# Connectors.net
KiCad netlist of a schematic drawn in Altium Designer
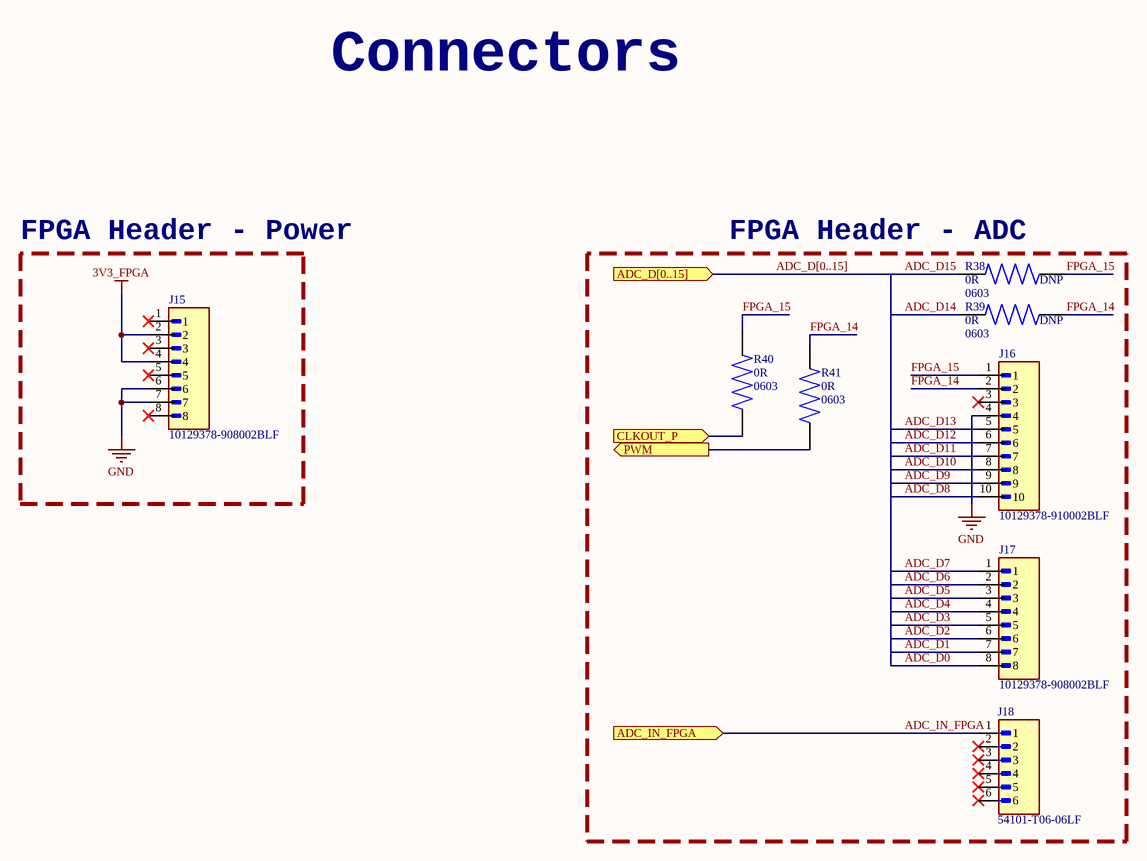
[diagram p0: Connectors.SchDoc]

(export (version "E")
  (design (tool "Eeschema 10.0.6"))
  (components
    (comp (ref "J15")
      (value "10129378-908002BLF")
      (footprint "AMPHENOL_10129378-908002BLF")
      (fields (field (name "MF") "Amphenol"))
      (libsource (lib "ETS_Library") (part "10129378-908002BLF"))
    )
    (comp (ref "J16")
      (value "10129378-910002BLF")
      (footprint "AMPHENOL_10129378-910002BLF")
      (libsource (lib "ETS_Library") (part "10129378-910002BLF"))
    )
    (comp (ref "J17")
      (value "10129378-908002BLF")
      (footprint "AMPHENOL_10129378-908002BLF")
      (fields (field (name "MF") "Amphenol"))
      (libsource (lib "ETS_Library") (part "10129378-908002BLF"))
    )
    (comp (ref "J18")
      (value "54101-T06-06LF")
      (footprint "AMPHENOL_54101-T06-06LF")
      (fields (field (name "MF") "Amphenol ICC (FCI)"))
      (libsource (lib "ETS_Library") (part "54101-T06-06LF"))
    )
    (comp (ref "R38")
      (value "0R")
      (footprint "RESC1508X55N")
      (description "0 Ohms Jumper 0.1W, 1/10W Chip Resistor 0603 (1608 Metric) Automotive AEC-Q200 Thick Film")
      (fields
        (field (name "PACKAGE") "0603")
        (field (name "MF") "Stackpole Electronics")
        (field (name "MP") "RMCF0603ZT0R00")
      )
      (libsource (lib "ETS_Library") (part "RMCF0603ZT0R00"))
    )
    (comp (ref "R39")
      (value "0R")
      (footprint "RESC1508X55N")
      (description "0 Ohms Jumper 0.1W, 1/10W Chip Resistor 0603 (1608 Metric) Automotive AEC-Q200 Thick Film")
      (fields
        (field (name "PACKAGE") "0603")
        (field (name "MF") "Stackpole Electronics")
        (field (name "MP") "RMCF0603ZT0R00")
      )
      (libsource (lib "ETS_Library") (part "RMCF0603ZT0R00"))
    )
    (comp (ref "R40")
      (value "0R")
      (footprint "RESC1508X55N")
      (description "0 Ohms Jumper 0.1W, 1/10W Chip Resistor 0603 (1608 Metric) Automotive AEC-Q200 Thick Film")
      (fields
        (field (name "PACKAGE") "0603")
        (field (name "MF") "Stackpole Electronics")
        (field (name "MP") "RMCF0603ZT0R00")
      )
      (libsource (lib "ETS_Library") (part "RMCF0603ZT0R00"))
    )
    (comp (ref "R41")
      (value "0R")
      (footprint "RESC1508X55N")
      (description "0 Ohms Jumper 0.1W, 1/10W Chip Resistor 0603 (1608 Metric) Automotive AEC-Q200 Thick Film")
      (fields
        (field (name "PACKAGE") "0603")
        (field (name "MF") "Stackpole Electronics")
        (field (name "MP") "RMCF0603ZT0R00")
      )
      (libsource (lib "ETS_Library") (part "RMCF0603ZT0R00"))
    )
  )
  (nets
    (net (code "1") (name "/ADC_D0") (class "Default")
      (node (ref "J17") (pin "8") (pinfunction "8_8") (pintype "passive"))
    )
    (net (code "2") (name "/ADC_D1") (class "Default")
      (node (ref "J17") (pin "7") (pinfunction "7_7") (pintype "passive"))
    )
    (net (code "3") (name "/ADC_D2") (class "Default")
      (node (ref "J17") (pin "6") (pinfunction "6_6") (pintype "passive"))
    )
    (net (code "4") (name "/ADC_D3") (class "Default")
      (node (ref "J17") (pin "5") (pinfunction "5_5") (pintype "passive"))
    )
    (net (code "5") (name "/ADC_D4") (class "Default")
      (node (ref "J17") (pin "4") (pinfunction "4_4") (pintype "passive"))
    )
    (net (code "6") (name "/ADC_D5") (class "Default")
      (node (ref "J17") (pin "3") (pinfunction "3_3") (pintype "passive"))
    )
    (net (code "7") (name "/ADC_D6") (class "Default")
      (node (ref "J17") (pin "2") (pinfunction "2_2") (pintype "passive"))
    )
    (net (code "8") (name "/ADC_D7") (class "Default")
      (node (ref "J17") (pin "1") (pinfunction "1_1") (pintype "passive"))
    )
    (net (code "9") (name "/ADC_D8") (class "Default")
      (node (ref "J16") (pin "10") (pinfunction "10_10") (pintype "passive"))
    )
    (net (code "10") (name "/ADC_D9") (class "Default")
      (node (ref "J16") (pin "9") (pinfunction "9_9") (pintype "passive"))
    )
    (net (code "11") (name "/ADC_D10") (class "Default")
      (node (ref "J16") (pin "8") (pinfunction "8_8") (pintype "passive"))
    )
    (net (code "12") (name "/ADC_D11") (class "Default")
      (node (ref "J16") (pin "7") (pinfunction "7_7") (pintype "passive"))
    )
    (net (code "13") (name "/ADC_D12") (class "Default")
      (node (ref "J16") (pin "6") (pinfunction "6_6") (pintype "passive"))
    )
    (net (code "14") (name "/ADC_D13") (class "Default")
      (node (ref "J16") (pin "5") (pinfunction "5_5") (pintype "passive"))
    )
    (net (code "15") (name "/ADC_D14") (class "Default")
      (node (ref "R39") (pin "1") (pinfunction "1_1") (pintype "passive"))
    )
    (net (code "16") (name "/ADC_D15") (class "Default")
      (node (ref "R38") (pin "1") (pinfunction "1_1") (pintype "passive"))
    )
    (net (code "18") (name "/ADC_IN_FPGA") (class "Default")
      (node (ref "J18") (pin "1") (pinfunction "1_1") (pintype "passive"))
    )
    (net (code "19") (name "/CLKOUT_P") (class "Default")
      (node (ref "R40") (pin "1") (pinfunction "1_1") (pintype "passive"))
    )
    (net (code "20") (name "/FPGA_14") (class "Default")
      (node (ref "J16") (pin "2") (pinfunction "2_2") (pintype "passive"))
      (node (ref "R39") (pin "2") (pinfunction "2_2") (pintype "passive"))
      (node (ref "R41") (pin "2") (pinfunction "2_2") (pintype "passive"))
    )
    (net (code "21") (name "/FPGA_15") (class "Default")
      (node (ref "J16") (pin "1") (pinfunction "1_1") (pintype "passive"))
      (node (ref "R38") (pin "2") (pinfunction "2_2") (pintype "passive"))
      (node (ref "R40") (pin "2") (pinfunction "2_2") (pintype "passive"))
    )
    (net (code "22") (name "/PWM") (class "Default")
      (node (ref "R41") (pin "1") (pinfunction "1_1") (pintype "passive"))
    )
    (net (code "23") (name "3V3_FPGA") (class "Default")
      (node (ref "J15") (pin "2") (pinfunction "2_2") (pintype "passive"))
      (node (ref "J15") (pin "4") (pinfunction "4_4") (pintype "passive"))
    )
    (net (code "24") (name "GND") (class "Default")
      (node (ref "J15") (pin "6") (pinfunction "6_6") (pintype "passive"))
      (node (ref "J15") (pin "7") (pinfunction "7_7") (pintype "passive"))
      (node (ref "J16") (pin "4") (pinfunction "4_4") (pintype "passive"))
    )
    (net (code "25") (name "unconnected-(J15-Pad1)") (class "Default")
      (node (ref "J15") (pin "1") (pinfunction "1_1") (pintype "passive+no_connect"))
    )
    (net (code "26") (name "unconnected-(J15-Pad3)") (class "Default")
      (node (ref "J15") (pin "3") (pinfunction "3_3") (pintype "passive+no_connect"))
    )
    (net (code "27") (name "unconnected-(J15-Pad5)") (class "Default")
      (node (ref "J15") (pin "5") (pinfunction "5_5") (pintype "passive+no_connect"))
    )
    (net (code "28") (name "unconnected-(J15-Pad8)") (class "Default")
      (node (ref "J15") (pin "8") (pinfunction "8_8") (pintype "passive+no_connect"))
    )
    (net (code "29") (name "unconnected-(J16-Pad3)") (class "Default")
      (node (ref "J16") (pin "3") (pinfunction "3_3") (pintype "passive+no_connect"))
    )
    (net (code "30") (name "unconnected-(J18-Pad2)") (class "Default")
      (node (ref "J18") (pin "2") (pinfunction "2_2") (pintype "passive+no_connect"))
    )
    (net (code "31") (name "unconnected-(J18-Pad3)") (class "Default")
      (node (ref "J18") (pin "3") (pinfunction "3_3") (pintype "passive+no_connect"))
    )
    (net (code "32") (name "unconnected-(J18-Pad4)") (class "Default")
      (node (ref "J18") (pin "4") (pinfunction "4_4") (pintype "passive+no_connect"))
    )
    (net (code "33") (name "unconnected-(J18-Pad5)") (class "Default")
      (node (ref "J18") (pin "5") (pinfunction "5_5") (pintype "passive+no_connect"))
    )
    (net (code "34") (name "unconnected-(J18-Pad6)") (class "Default")
      (node (ref "J18") (pin "6") (pinfunction "6_6") (pintype "passive+no_connect"))
    )
  )
)
